# Side_Long_IXYS.net
KiCad netlist of a schematic drawn in EAGLE
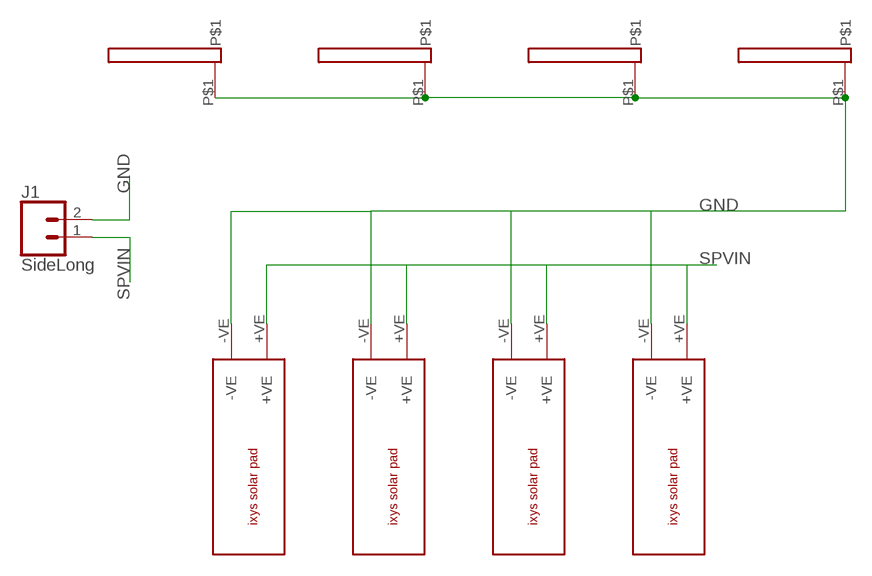
[diagram p0: schematic, sheet 1]

(export (version "E")
  (design (tool "Eeschema 10.0.6"))
  (components
    (comp (ref "J1")
      (value "SideLong")
      (footprint "eagle-import:1X02")
      (libsource (lib "eagle-import") (part "CONN_02"))
    )
    (comp (ref "U$1")
      (value "16X2")
      (footprint "eagle-import:16X2")
      (libsource (lib "eagle-import") (part "16X2"))
    )
    (comp (ref "U$2")
      (value "16X2")
      (footprint "eagle-import:16X2")
      (libsource (lib "eagle-import") (part "16X2"))
    )
    (comp (ref "U$3")
      (value "16X2")
      (footprint "eagle-import:16X2")
      (libsource (lib "eagle-import") (part "16X2"))
    )
    (comp (ref "U$4")
      (value "16X2")
      (footprint "eagle-import:16X2")
      (libsource (lib "eagle-import") (part "16X2"))
    )
    (comp (ref "U$9")
      (value "IXYS")
      (footprint "eagle-import:IXYS")
      (libsource (lib "eagle-import") (part "IXYS"))
    )
    (comp (ref "U$10")
      (value "IXYS")
      (footprint "eagle-import:IXYS")
      (libsource (lib "eagle-import") (part "IXYS"))
    )
    (comp (ref "U$11")
      (value "IXYS")
      (footprint "eagle-import:IXYS")
      (libsource (lib "eagle-import") (part "IXYS"))
    )
    (comp (ref "U$12")
      (value "IXYS")
      (footprint "eagle-import:IXYS")
      (libsource (lib "eagle-import") (part "IXYS"))
    )
  )
  (nets
    (net (code "1") (name "/GND") (class "Default")
      (node (ref "J1") (pin "2") (pinfunction "2_2") (pintype "passive"))
      (node (ref "U$1") (pin "P$1") (pinfunction "P$1_P$1") (pintype "bidirectional"))
      (node (ref "U$10") (pin "-VE") (pinfunction "-VE_-VE") (pintype "bidirectional"))
      (node (ref "U$11") (pin "-VE") (pinfunction "-VE_-VE") (pintype "bidirectional"))
      (node (ref "U$12") (pin "-VE") (pinfunction "-VE_-VE") (pintype "bidirectional"))
      (node (ref "U$2") (pin "P$1") (pinfunction "P$1_P$1") (pintype "bidirectional"))
      (node (ref "U$3") (pin "P$1") (pinfunction "P$1_P$1") (pintype "bidirectional"))
      (node (ref "U$4") (pin "P$1") (pinfunction "P$1_P$1") (pintype "bidirectional"))
      (node (ref "U$9") (pin "-VE") (pinfunction "-VE_-VE") (pintype "bidirectional"))
    )
    (net (code "2") (name "/SPVIN") (class "Default")
      (node (ref "J1") (pin "1") (pinfunction "1_1") (pintype "passive"))
      (node (ref "U$10") (pin "+VE") (pinfunction "+VE_+VE") (pintype "bidirectional"))
      (node (ref "U$11") (pin "+VE") (pinfunction "+VE_+VE") (pintype "bidirectional"))
      (node (ref "U$12") (pin "+VE") (pinfunction "+VE_+VE") (pintype "bidirectional"))
      (node (ref "U$9") (pin "+VE") (pinfunction "+VE_+VE") (pintype "bidirectional"))
    )
  )
)
